# DDR_MIO.net
KiCad netlist of a schematic drawn in Altium Designer
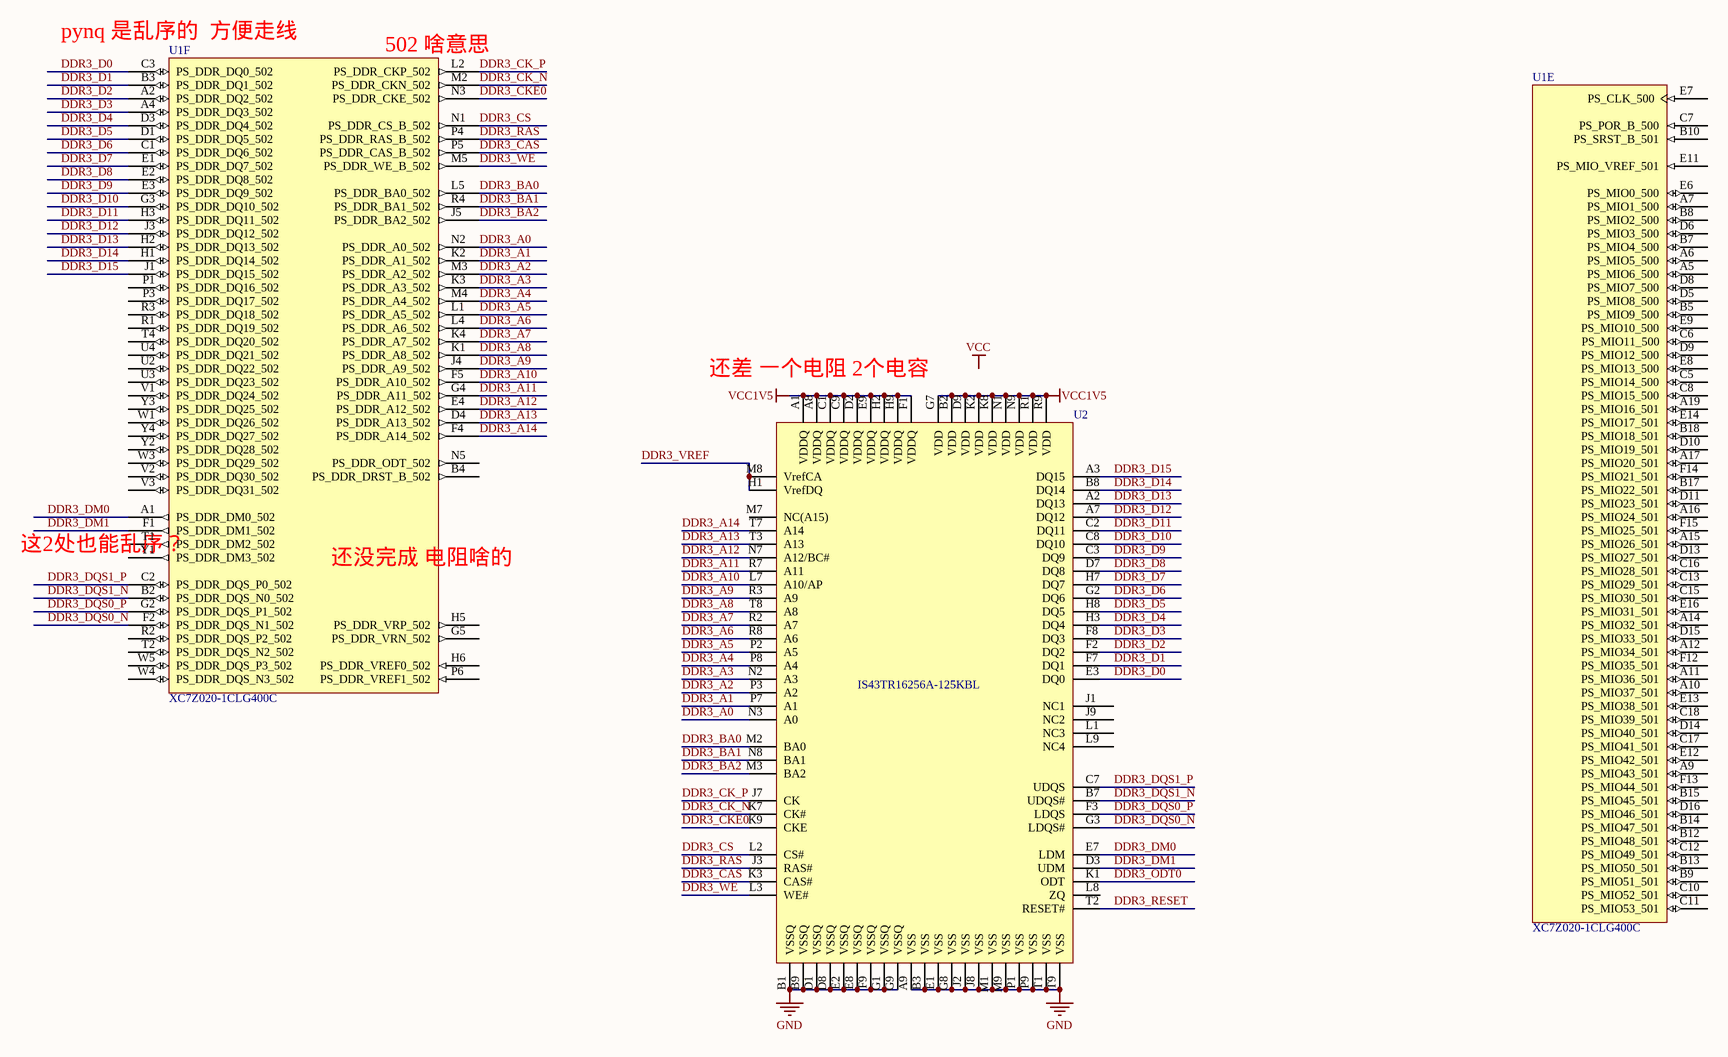
[diagram p0: DDR&MIO.SchDoc]

(export (version "E")
  (design (tool "Eeschema 10.0.6"))
  (components
    (comp (ref "U1")
      (value "XC7Z020-1CLG400C")
      (footprint "CLG400")
      (fields (field (name "GENERIC PART NUMBER") "XC7Z020") (field (name "MANUFACTURER") "Xilinx"))
      (libsource (lib "Zynq-7000") (part "XC7Z020-1CLG400C"))
    )
    (comp (ref "U2")
      (value "IS43TR16256A-125KBL")
      (footprint "BGA96C80P16X9_1400X900X120")
      (description "与MT41K256M16HA-125IT完全兼容")
      (libsource (lib "misc1") (part "IS43TR16256A-125KBL"))
    )
  )
  (nets
    (net (code "1") (name "/DDR3_A0") (class "Default")
      (node (ref "U1") (pin "N2") (pinfunction "PS_DDR_A0_502_N2") (pintype "output"))
      (node (ref "U2") (pin "N3") (pinfunction "A0_N3") (pintype "passive"))
    )
    (net (code "2") (name "/DDR3_A1") (class "Default")
      (node (ref "U1") (pin "K2") (pinfunction "PS_DDR_A1_502_K2") (pintype "output"))
      (node (ref "U2") (pin "P7") (pinfunction "A1_P7") (pintype "passive"))
    )
    (net (code "3") (name "/DDR3_A2") (class "Default")
      (node (ref "U1") (pin "M3") (pinfunction "PS_DDR_A2_502_M3") (pintype "output"))
      (node (ref "U2") (pin "P3") (pinfunction "A2_P3") (pintype "passive"))
    )
    (net (code "4") (name "/DDR3_A3") (class "Default")
      (node (ref "U1") (pin "K3") (pinfunction "PS_DDR_A3_502_K3") (pintype "output"))
      (node (ref "U2") (pin "N2") (pinfunction "A3_N2") (pintype "passive"))
    )
    (net (code "5") (name "/DDR3_A4") (class "Default")
      (node (ref "U1") (pin "M4") (pinfunction "PS_DDR_A4_502_M4") (pintype "output"))
      (node (ref "U2") (pin "P8") (pinfunction "A4_P8") (pintype "passive"))
    )
    (net (code "6") (name "/DDR3_A5") (class "Default")
      (node (ref "U1") (pin "L1") (pinfunction "PS_DDR_A5_502_L1") (pintype "output"))
      (node (ref "U2") (pin "P2") (pinfunction "A5_P2") (pintype "passive"))
    )
    (net (code "7") (name "/DDR3_A6") (class "Default")
      (node (ref "U1") (pin "L4") (pinfunction "PS_DDR_A6_502_L4") (pintype "output"))
      (node (ref "U2") (pin "R8") (pinfunction "A6_R8") (pintype "passive"))
    )
    (net (code "8") (name "/DDR3_A7") (class "Default")
      (node (ref "U1") (pin "K4") (pinfunction "PS_DDR_A7_502_K4") (pintype "output"))
      (node (ref "U2") (pin "R2") (pinfunction "A7_R2") (pintype "passive"))
    )
    (net (code "9") (name "/DDR3_A8") (class "Default")
      (node (ref "U1") (pin "K1") (pinfunction "PS_DDR_A8_502_K1") (pintype "output"))
      (node (ref "U2") (pin "T8") (pinfunction "A8_T8") (pintype "passive"))
    )
    (net (code "10") (name "/DDR3_A9") (class "Default")
      (node (ref "U1") (pin "J4") (pinfunction "PS_DDR_A9_502_J4") (pintype "output"))
      (node (ref "U2") (pin "R3") (pinfunction "A9_R3") (pintype "passive"))
    )
    (net (code "11") (name "/DDR3_A10") (class "Default")
      (node (ref "U1") (pin "F5") (pinfunction "PS_DDR_A10_502_F5") (pintype "output"))
      (node (ref "U2") (pin "L7") (pinfunction "A10/AP_L7") (pintype "passive"))
    )
    (net (code "12") (name "/DDR3_A11") (class "Default")
      (node (ref "U1") (pin "G4") (pinfunction "PS_DDR_A11_502_G4") (pintype "output"))
      (node (ref "U2") (pin "R7") (pinfunction "A11_R7") (pintype "passive"))
    )
    (net (code "13") (name "/DDR3_A12") (class "Default")
      (node (ref "U1") (pin "E4") (pinfunction "PS_DDR_A12_502_E4") (pintype "output"))
      (node (ref "U2") (pin "N7") (pinfunction "A12/BC#_N7") (pintype "passive"))
    )
    (net (code "14") (name "/DDR3_A13") (class "Default")
      (node (ref "U1") (pin "D4") (pinfunction "PS_DDR_A13_502_D4") (pintype "output"))
      (node (ref "U2") (pin "T3") (pinfunction "A13_T3") (pintype "passive"))
    )
    (net (code "15") (name "/DDR3_A14") (class "Default")
      (node (ref "U1") (pin "F4") (pinfunction "PS_DDR_A14_502_F4") (pintype "output"))
      (node (ref "U2") (pin "T7") (pinfunction "A14_T7") (pintype "passive"))
    )
    (net (code "16") (name "/DDR3_BA0") (class "Default")
      (node (ref "U1") (pin "L5") (pinfunction "PS_DDR_BA0_502_L5") (pintype "output"))
      (node (ref "U2") (pin "M2") (pinfunction "BA0_M2") (pintype "passive"))
    )
    (net (code "17") (name "/DDR3_BA1") (class "Default")
      (node (ref "U1") (pin "R4") (pinfunction "PS_DDR_BA1_502_R4") (pintype "output"))
      (node (ref "U2") (pin "N8") (pinfunction "BA1_N8") (pintype "passive"))
    )
    (net (code "18") (name "/DDR3_BA2") (class "Default")
      (node (ref "U1") (pin "J5") (pinfunction "PS_DDR_BA2_502_J5") (pintype "output"))
      (node (ref "U2") (pin "M3") (pinfunction "BA2_M3") (pintype "passive"))
    )
    (net (code "19") (name "/DDR3_CAS") (class "Default")
      (node (ref "U1") (pin "P5") (pinfunction "PS_DDR_CAS_B_502_P5") (pintype "output"))
      (node (ref "U2") (pin "K3") (pinfunction "CAS#_K3") (pintype "passive"))
    )
    (net (code "20") (name "/DDR3_CKE0") (class "Default")
      (node (ref "U1") (pin "N3") (pinfunction "PS_DDR_CKE_502_N3") (pintype "output"))
      (node (ref "U2") (pin "K9") (pinfunction "CKE_K9") (pintype "passive"))
    )
    (net (code "21") (name "/DDR3_CK_N") (class "Default")
      (node (ref "U1") (pin "M2") (pinfunction "PS_DDR_CKN_502_M2") (pintype "output"))
      (node (ref "U2") (pin "K7") (pinfunction "CK#_K7") (pintype "passive"))
    )
    (net (code "22") (name "/DDR3_CK_P") (class "Default")
      (node (ref "U1") (pin "L2") (pinfunction "PS_DDR_CKP_502_L2") (pintype "output"))
      (node (ref "U2") (pin "J7") (pinfunction "CK_J7") (pintype "passive"))
    )
    (net (code "23") (name "/DDR3_CS") (class "Default")
      (node (ref "U1") (pin "N1") (pinfunction "PS_DDR_CS_B_502_N1") (pintype "output"))
      (node (ref "U2") (pin "L2") (pinfunction "CS#_L2") (pintype "passive"))
    )
    (net (code "24") (name "/DDR3_D0") (class "Default")
      (node (ref "U1") (pin "C3") (pinfunction "PS_DDR_DQ0_502_C3") (pintype "bidirectional"))
      (node (ref "U2") (pin "E3") (pinfunction "DQ0_E3") (pintype "passive"))
    )
    (net (code "25") (name "/DDR3_D1") (class "Default")
      (node (ref "U1") (pin "B3") (pinfunction "PS_DDR_DQ1_502_B3") (pintype "bidirectional"))
      (node (ref "U2") (pin "F7") (pinfunction "DQ1_F7") (pintype "passive"))
    )
    (net (code "26") (name "/DDR3_D2") (class "Default")
      (node (ref "U1") (pin "A2") (pinfunction "PS_DDR_DQ2_502_A2") (pintype "bidirectional"))
      (node (ref "U2") (pin "F2") (pinfunction "DQ2_F2") (pintype "passive"))
    )
    (net (code "27") (name "/DDR3_D3") (class "Default")
      (node (ref "U1") (pin "A4") (pinfunction "PS_DDR_DQ3_502_A4") (pintype "bidirectional"))
      (node (ref "U2") (pin "F8") (pinfunction "DQ3_F8") (pintype "passive"))
    )
    (net (code "28") (name "/DDR3_D4") (class "Default")
      (node (ref "U1") (pin "D3") (pinfunction "PS_DDR_DQ4_502_D3") (pintype "bidirectional"))
      (node (ref "U2") (pin "H3") (pinfunction "DQ4_H3") (pintype "passive"))
    )
    (net (code "29") (name "/DDR3_D5") (class "Default")
      (node (ref "U1") (pin "D1") (pinfunction "PS_DDR_DQ5_502_D1") (pintype "bidirectional"))
      (node (ref "U2") (pin "H8") (pinfunction "DQ5_H8") (pintype "passive"))
    )
    (net (code "30") (name "/DDR3_D6") (class "Default")
      (node (ref "U1") (pin "C1") (pinfunction "PS_DDR_DQ6_502_C1") (pintype "bidirectional"))
      (node (ref "U2") (pin "G2") (pinfunction "DQ6_G2") (pintype "passive"))
    )
    (net (code "31") (name "/DDR3_D7") (class "Default")
      (node (ref "U1") (pin "E1") (pinfunction "PS_DDR_DQ7_502_E1") (pintype "bidirectional"))
      (node (ref "U2") (pin "H7") (pinfunction "DQ7_H7") (pintype "passive"))
    )
    (net (code "32") (name "/DDR3_D8") (class "Default")
      (node (ref "U1") (pin "E2") (pinfunction "PS_DDR_DQ8_502_E2") (pintype "bidirectional"))
      (node (ref "U2") (pin "D7") (pinfunction "DQ8_D7") (pintype "passive"))
    )
    (net (code "33") (name "/DDR3_D9") (class "Default")
      (node (ref "U1") (pin "E3") (pinfunction "PS_DDR_DQ9_502_E3") (pintype "bidirectional"))
      (node (ref "U2") (pin "C3") (pinfunction "DQ9_C3") (pintype "passive"))
    )
    (net (code "34") (name "/DDR3_D10") (class "Default")
      (node (ref "U1") (pin "G3") (pinfunction "PS_DDR_DQ10_502_G3") (pintype "bidirectional"))
      (node (ref "U2") (pin "C8") (pinfunction "DQ10_C8") (pintype "passive"))
    )
    (net (code "35") (name "/DDR3_D11") (class "Default")
      (node (ref "U1") (pin "H3") (pinfunction "PS_DDR_DQ11_502_H3") (pintype "bidirectional"))
      (node (ref "U2") (pin "C2") (pinfunction "DQ11_C2") (pintype "passive"))
    )
    (net (code "36") (name "/DDR3_D12") (class "Default")
      (node (ref "U1") (pin "J3") (pinfunction "PS_DDR_DQ12_502_J3") (pintype "bidirectional"))
      (node (ref "U2") (pin "A7") (pinfunction "DQ12_A7") (pintype "passive"))
    )
    (net (code "37") (name "/DDR3_D13") (class "Default")
      (node (ref "U1") (pin "H2") (pinfunction "PS_DDR_DQ13_502_H2") (pintype "bidirectional"))
      (node (ref "U2") (pin "A2") (pinfunction "DQ13_A2") (pintype "passive"))
    )
    (net (code "38") (name "/DDR3_D14") (class "Default")
      (node (ref "U1") (pin "H1") (pinfunction "PS_DDR_DQ14_502_H1") (pintype "bidirectional"))
      (node (ref "U2") (pin "B8") (pinfunction "DQ14_B8") (pintype "passive"))
    )
    (net (code "39") (name "/DDR3_D15") (class "Default")
      (node (ref "U1") (pin "J1") (pinfunction "PS_DDR_DQ15_502_J1") (pintype "bidirectional"))
      (node (ref "U2") (pin "A3") (pinfunction "DQ15_A3") (pintype "passive"))
    )
    (net (code "40") (name "/DDR3_DM0") (class "Default")
      (node (ref "U1") (pin "A1") (pinfunction "PS_DDR_DM0_502_A1") (pintype "output"))
      (node (ref "U2") (pin "E7") (pinfunction "LDM_E7") (pintype "passive"))
    )
    (net (code "41") (name "/DDR3_DM1") (class "Default")
      (node (ref "U1") (pin "F1") (pinfunction "PS_DDR_DM1_502_F1") (pintype "output"))
      (node (ref "U2") (pin "D3") (pinfunction "UDM_D3") (pintype "passive"))
    )
    (net (code "42") (name "/DDR3_DQS0_N") (class "Default")
      (node (ref "U1") (pin "F2") (pinfunction "PS_DDR_DQS_N1_502_F2") (pintype "bidirectional"))
      (node (ref "U2") (pin "G3") (pinfunction "LDQS#_G3") (pintype "passive"))
    )
    (net (code "43") (name "/DDR3_DQS0_P") (class "Default")
      (node (ref "U1") (pin "G2") (pinfunction "PS_DDR_DQS_P1_502_G2") (pintype "bidirectional"))
      (node (ref "U2") (pin "F3") (pinfunction "LDQS_F3") (pintype "passive"))
    )
    (net (code "44") (name "/DDR3_DQS1_N") (class "Default")
      (node (ref "U1") (pin "B2") (pinfunction "PS_DDR_DQS_N0_502_B2") (pintype "bidirectional"))
      (node (ref "U2") (pin "B7") (pinfunction "UDQS#_B7") (pintype "passive"))
    )
    (net (code "45") (name "/DDR3_DQS1_P") (class "Default")
      (node (ref "U1") (pin "C2") (pinfunction "PS_DDR_DQS_P0_502_C2") (pintype "bidirectional"))
      (node (ref "U2") (pin "C7") (pinfunction "UDQS_C7") (pintype "passive"))
    )
    (net (code "46") (name "/DDR3_ODT0") (class "Default")
      (node (ref "U2") (pin "K1") (pinfunction "ODT_K1") (pintype "passive"))
    )
    (net (code "47") (name "/DDR3_RAS") (class "Default")
      (node (ref "U1") (pin "P4") (pinfunction "PS_DDR_RAS_B_502_P4") (pintype "output"))
      (node (ref "U2") (pin "J3") (pinfunction "RAS#_J3") (pintype "passive"))
    )
    (net (code "48") (name "/DDR3_RESET") (class "Default")
      (node (ref "U2") (pin "T2") (pinfunction "RESET#_T2") (pintype "passive"))
    )
    (net (code "49") (name "/DDR3_VREF") (class "Default")
      (node (ref "U2") (pin "H1") (pinfunction "VrefDQ_H1") (pintype "passive"))
      (node (ref "U2") (pin "M8") (pinfunction "VrefCA_M8") (pintype "passive"))
    )
    (net (code "50") (name "/DDR3_WE") (class "Default")
      (node (ref "U1") (pin "M5") (pinfunction "PS_DDR_WE_B_502_M5") (pintype "output"))
      (node (ref "U2") (pin "L3") (pinfunction "WE#_L3") (pintype "passive"))
    )
    (net (code "51") (name "GND") (class "Default")
      (node (ref "U2") (pin "A9") (pinfunction "VSS_A9") (pintype "passive"))
      (node (ref "U2") (pin "B1") (pinfunction "VSSQ_B1") (pintype "passive"))
      (node (ref "U2") (pin "B3") (pinfunction "VSS_B3") (pintype "passive"))
      (node (ref "U2") (pin "B9") (pinfunction "VSSQ_B9") (pintype "passive"))
      (node (ref "U2") (pin "D1") (pinfunction "VSSQ_D1") (pintype "passive"))
      (node (ref "U2") (pin "D8") (pinfunction "VSSQ_D8") (pintype "passive"))
      (node (ref "U2") (pin "E1") (pinfunction "VSS_E1") (pintype "passive"))
      (node (ref "U2") (pin "E2") (pinfunction "VSSQ_E2") (pintype "passive"))
      (node (ref "U2") (pin "E8") (pinfunction "VSSQ_E8") (pintype "passive"))
      (node (ref "U2") (pin "F9") (pinfunction "VSSQ_F9") (pintype "passive"))
      (node (ref "U2") (pin "G1") (pinfunction "VSSQ_G1") (pintype "passive"))
      (node (ref "U2") (pin "G8") (pinfunction "VSS_G8") (pintype "passive"))
      (node (ref "U2") (pin "G9") (pinfunction "VSSQ_G9") (pintype "passive"))
      (node (ref "U2") (pin "J2") (pinfunction "VSS_J2") (pintype "passive"))
      (node (ref "U2") (pin "J8") (pinfunction "VSS_J8") (pintype "passive"))
      (node (ref "U2") (pin "M1") (pinfunction "VSS_M1") (pintype "passive"))
      (node (ref "U2") (pin "M9") (pinfunction "VSS_M9") (pintype "passive"))
      (node (ref "U2") (pin "P1") (pinfunction "VSS_P1") (pintype "passive"))
      (node (ref "U2") (pin "P9") (pinfunction "VSS_P9") (pintype "passive"))
      (node (ref "U2") (pin "T1") (pinfunction "VSS_T1") (pintype "passive"))
      (node (ref "U2") (pin "T9") (pinfunction "VSS_T9") (pintype "passive"))
    )
    (net (code "53") (name "VCC1V5") (class "Default")
      (node (ref "U2") (pin "A1") (pinfunction "VDDQ_A1") (pintype "passive"))
      (node (ref "U2") (pin "A8") (pinfunction "VDDQ_A8") (pintype "passive"))
      (node (ref "U2") (pin "B2") (pinfunction "VDD_B2") (pintype "passive"))
      (node (ref "U2") (pin "C1") (pinfunction "VDDQ_C1") (pintype "passive"))
      (node (ref "U2") (pin "C9") (pinfunction "VDDQ_C9") (pintype "passive"))
      (node (ref "U2") (pin "D2") (pinfunction "VDDQ_D2") (pintype "passive"))
      (node (ref "U2") (pin "D9") (pinfunction "VDD_D9") (pintype "passive"))
      (node (ref "U2") (pin "E9") (pinfunction "VDDQ_E9") (pintype "passive"))
      (node (ref "U2") (pin "F1") (pinfunction "VDDQ_F1") (pintype "passive"))
      (node (ref "U2") (pin "G7") (pinfunction "VDD_G7") (pintype "passive"))
      (node (ref "U2") (pin "H2") (pinfunction "VDDQ_H2") (pintype "passive"))
      (node (ref "U2") (pin "H9") (pinfunction "VDDQ_H9") (pintype "passive"))
      (node (ref "U2") (pin "K2") (pinfunction "VDD_K2") (pintype "passive"))
      (node (ref "U2") (pin "K8") (pinfunction "VDD_K8") (pintype "passive"))
      (node (ref "U2") (pin "N1") (pinfunction "VDD_N1") (pintype "passive"))
      (node (ref "U2") (pin "N9") (pinfunction "VDD_N9") (pintype "passive"))
      (node (ref "U2") (pin "R1") (pinfunction "VDD_R1") (pintype "passive"))
      (node (ref "U2") (pin "R9") (pinfunction "VDD_R9") (pintype "passive"))
    )
    (net (code "54") (name "unconnected-(U1E-PS_CLK_500-PadE7)") (class "Default")
      (node (ref "U1") (pin "E7") (pinfunction "PS_CLK_500_E7") (pintype "input"))
    )
    (net (code "55") (name "unconnected-(U1E-PS_MIO0_500-PadE6)") (class "Default")
      (node (ref "U1") (pin "E6") (pinfunction "PS_MIO0_500_E6") (pintype "bidirectional"))
    )
    (net (code "56") (name "unconnected-(U1E-PS_MIO1_500-PadA7)") (class "Default")
      (node (ref "U1") (pin "A7") (pinfunction "PS_MIO1_500_A7") (pintype "bidirectional"))
    )
    (net (code "57") (name "unconnected-(U1E-PS_MIO2_500-PadB8)") (class "Default")
      (node (ref "U1") (pin "B8") (pinfunction "PS_MIO2_500_B8") (pintype "bidirectional"))
    )
    (net (code "58") (name "unconnected-(U1E-PS_MIO3_500-PadD6)") (class "Default")
      (node (ref "U1") (pin "D6") (pinfunction "PS_MIO3_500_D6") (pintype "bidirectional"))
    )
    (net (code "59") (name "unconnected-(U1E-PS_MIO4_500-PadB7)") (class "Default")
      (node (ref "U1") (pin "B7") (pinfunction "PS_MIO4_500_B7") (pintype "bidirectional"))
    )
    (net (code "60") (name "unconnected-(U1E-PS_MIO5_500-PadA6)") (class "Default")
      (node (ref "U1") (pin "A6") (pinfunction "PS_MIO5_500_A6") (pintype "bidirectional"))
    )
    (net (code "61") (name "unconnected-(U1E-PS_MIO6_500-PadA5)") (class "Default")
      (node (ref "U1") (pin "A5") (pinfunction "PS_MIO6_500_A5") (pintype "bidirectional"))
    )
    (net (code "62") (name "unconnected-(U1E-PS_MIO7_500-PadD8)") (class "Default")
      (node (ref "U1") (pin "D8") (pinfunction "PS_MIO7_500_D8") (pintype "bidirectional"))
    )
    (net (code "63") (name "unconnected-(U1E-PS_MIO8_500-PadD5)") (class "Default")
      (node (ref "U1") (pin "D5") (pinfunction "PS_MIO8_500_D5") (pintype "bidirectional"))
    )
    (net (code "64") (name "unconnected-(U1E-PS_MIO9_500-PadB5)") (class "Default")
      (node (ref "U1") (pin "B5") (pinfunction "PS_MIO9_500_B5") (pintype "bidirectional"))
    )
    (net (code "65") (name "unconnected-(U1E-PS_MIO10_500-PadE9)") (class "Default")
      (node (ref "U1") (pin "E9") (pinfunction "PS_MIO10_500_E9") (pintype "bidirectional"))
    )
    (net (code "66") (name "unconnected-(U1E-PS_MIO11_500-PadC6)") (class "Default")
      (node (ref "U1") (pin "C6") (pinfunction "PS_MIO11_500_C6") (pintype "bidirectional"))
    )
    (net (code "67") (name "unconnected-(U1E-PS_MIO12_500-PadD9)") (class "Default")
      (node (ref "U1") (pin "D9") (pinfunction "PS_MIO12_500_D9") (pintype "bidirectional"))
    )
    (net (code "68") (name "unconnected-(U1E-PS_MIO13_500-PadE8)") (class "Default")
      (node (ref "U1") (pin "E8") (pinfunction "PS_MIO13_500_E8") (pintype "bidirectional"))
    )
    (net (code "69") (name "unconnected-(U1E-PS_MIO14_500-PadC5)") (class "Default")
      (node (ref "U1") (pin "C5") (pinfunction "PS_MIO14_500_C5") (pintype "bidirectional"))
    )
    (net (code "70") (name "unconnected-(U1E-PS_MIO15_500-PadC8)") (class "Default")
      (node (ref "U1") (pin "C8") (pinfunction "PS_MIO15_500_C8") (pintype "bidirectional"))
    )
    (net (code "71") (name "unconnected-(U1E-PS_MIO16_501-PadA19)") (class "Default")
      (node (ref "U1") (pin "A19") (pinfunction "PS_MIO16_501_A19") (pintype "bidirectional"))
    )
    (net (code "72") (name "unconnected-(U1E-PS_MIO17_501-PadE14)") (class "Default")
      (node (ref "U1") (pin "E14") (pinfunction "PS_MIO17_501_E14") (pintype "bidirectional"))
    )
    (net (code "73") (name "unconnected-(U1E-PS_MIO18_501-PadB18)") (class "Default")
      (node (ref "U1") (pin "B18") (pinfunction "PS_MIO18_501_B18") (pintype "bidirectional"))
    )
    (net (code "74") (name "unconnected-(U1E-PS_MIO19_501-PadD10)") (class "Default")
      (node (ref "U1") (pin "D10") (pinfunction "PS_MIO19_501_D10") (pintype "bidirectional"))
    )
    (net (code "75") (name "unconnected-(U1E-PS_MIO20_501-PadA17)") (class "Default")
      (node (ref "U1") (pin "A17") (pinfunction "PS_MIO20_501_A17") (pintype "bidirectional"))
    )
    (net (code "76") (name "unconnected-(U1E-PS_MIO21_501-PadF14)") (class "Default")
      (node (ref "U1") (pin "F14") (pinfunction "PS_MIO21_501_F14") (pintype "bidirectional"))
    )
    (net (code "77") (name "unconnected-(U1E-PS_MIO22_501-PadB17)") (class "Default")
      (node (ref "U1") (pin "B17") (pinfunction "PS_MIO22_501_B17") (pintype "bidirectional"))
    )
    (net (code "78") (name "unconnected-(U1E-PS_MIO23_501-PadD11)") (class "Default")
      (node (ref "U1") (pin "D11") (pinfunction "PS_MIO23_501_D11") (pintype "bidirectional"))
    )
    (net (code "79") (name "unconnected-(U1E-PS_MIO24_501-PadA16)") (class "Default")
      (node (ref "U1") (pin "A16") (pinfunction "PS_MIO24_501_A16") (pintype "bidirectional"))
    )
    (net (code "80") (name "unconnected-(U1E-PS_MIO25_501-PadF15)") (class "Default")
      (node (ref "U1") (pin "F15") (pinfunction "PS_MIO25_501_F15") (pintype "bidirectional"))
    )
    (net (code "81") (name "unconnected-(U1E-PS_MIO26_501-PadA15)") (class "Default")
      (node (ref "U1") (pin "A15") (pinfunction "PS_MIO26_501_A15") (pintype "bidirectional"))
    )
    (net (code "82") (name "unconnected-(U1E-PS_MIO27_501-PadD13)") (class "Default")
      (node (ref "U1") (pin "D13") (pinfunction "PS_MIO27_501_D13") (pintype "bidirectional"))
    )
    (net (code "83") (name "unconnected-(U1E-PS_MIO28_501-PadC16)") (class "Default")
      (node (ref "U1") (pin "C16") (pinfunction "PS_MIO28_501_C16") (pintype "bidirectional"))
    )
    (net (code "84") (name "unconnected-(U1E-PS_MIO29_501-PadC13)") (class "Default")
      (node (ref "U1") (pin "C13") (pinfunction "PS_MIO29_501_C13") (pintype "bidirectional"))
    )
    (net (code "85") (name "unconnected-(U1E-PS_MIO30_501-PadC15)") (class "Default")
      (node (ref "U1") (pin "C15") (pinfunction "PS_MIO30_501_C15") (pintype "bidirectional"))
    )
    (net (code "86") (name "unconnected-(U1E-PS_MIO31_501-PadE16)") (class "Default")
      (node (ref "U1") (pin "E16") (pinfunction "PS_MIO31_501_E16") (pintype "bidirectional"))
    )
    (net (code "87") (name "unconnected-(U1E-PS_MIO32_501-PadA14)") (class "Default")
      (node (ref "U1") (pin "A14") (pinfunction "PS_MIO32_501_A14") (pintype "bidirectional"))
    )
    (net (code "88") (name "unconnected-(U1E-PS_MIO33_501-PadD15)") (class "Default")
      (node (ref "U1") (pin "D15") (pinfunction "PS_MIO33_501_D15") (pintype "bidirectional"))
    )
    (net (code "89") (name "unconnected-(U1E-PS_MIO34_501-PadA12)") (class "Default")
      (node (ref "U1") (pin "A12") (pinfunction "PS_MIO34_501_A12") (pintype "bidirectional"))
    )
    (net (code "90") (name "unconnected-(U1E-PS_MIO35_501-PadF12)") (class "Default")
      (node (ref "U1") (pin "F12") (pinfunction "PS_MIO35_501_F12") (pintype "bidirectional"))
    )
    (net (code "91") (name "unconnected-(U1E-PS_MIO36_501-PadA11)") (class "Default")
      (node (ref "U1") (pin "A11") (pinfunction "PS_MIO36_501_A11") (pintype "bidirectional"))
    )
    (net (code "92") (name "unconnected-(U1E-PS_MIO37_501-PadA10)") (class "Default")
      (node (ref "U1") (pin "A10") (pinfunction "PS_MIO37_501_A10") (pintype "bidirectional"))
    )
    (net (code "93") (name "unconnected-(U1E-PS_MIO38_501-PadE13)") (class "Default")
      (node (ref "U1") (pin "E13") (pinfunction "PS_MIO38_501_E13") (pintype "bidirectional"))
    )
    (net (code "94") (name "unconnected-(U1E-PS_MIO39_501-PadC18)") (class "Default")
      (node (ref "U1") (pin "C18") (pinfunction "PS_MIO39_501_C18") (pintype "bidirectional"))
    )
    (net (code "95") (name "unconnected-(U1E-PS_MIO40_501-PadD14)") (class "Default")
      (node (ref "U1") (pin "D14") (pinfunction "PS_MIO40_501_D14") (pintype "bidirectional"))
    )
    (net (code "96") (name "unconnected-(U1E-PS_MIO41_501-PadC17)") (class "Default")
      (node (ref "U1") (pin "C17") (pinfunction "PS_MIO41_501_C17") (pintype "bidirectional"))
    )
    (net (code "97") (name "unconnected-(U1E-PS_MIO42_501-PadE12)") (class "Default")
      (node (ref "U1") (pin "E12") (pinfunction "PS_MIO42_501_E12") (pintype "bidirectional"))
    )
    (net (code "98") (name "unconnected-(U1E-PS_MIO43_501-PadA9)") (class "Default")
      (node (ref "U1") (pin "A9") (pinfunction "PS_MIO43_501_A9") (pintype "bidirectional"))
    )
    (net (code "99") (name "unconnected-(U1E-PS_MIO44_501-PadF13)") (class "Default")
      (node (ref "U1") (pin "F13") (pinfunction "PS_MIO44_501_F13") (pintype "bidirectional"))
    )
    (net (code "100") (name "unconnected-(U1E-PS_MIO45_501-PadB15)") (class "Default")
      (node (ref "U1") (pin "B15") (pinfunction "PS_MIO45_501_B15") (pintype "bidirectional"))
    )
    (net (code "101") (name "unconnected-(U1E-PS_MIO46_501-PadD16)") (class "Default")
      (node (ref "U1") (pin "D16") (pinfunction "PS_MIO46_501_D16") (pintype "bidirectional"))
    )
    (net (code "102") (name "unconnected-(U1E-PS_MIO47_501-PadB14)") (class "Default")
      (node (ref "U1") (pin "B14") (pinfunction "PS_MIO47_501_B14") (pintype "bidirectional"))
    )
    (net (code "103") (name "unconnected-(U1E-PS_MIO48_501-PadB12)") (class "Default")
      (node (ref "U1") (pin "B12") (pinfunction "PS_MIO48_501_B12") (pintype "bidirectional"))
    )
    (net (code "104") (name "unconnected-(U1E-PS_MIO49_501-PadC12)") (class "Default")
      (node (ref "U1") (pin "C12") (pinfunction "PS_MIO49_501_C12") (pintype "bidirectional"))
    )
    (net (code "105") (name "unconnected-(U1E-PS_MIO50_501-PadB13)") (class "Default")
      (node (ref "U1") (pin "B13") (pinfunction "PS_MIO50_501_B13") (pintype "bidirectional"))
    )
    (net (code "106") (name "unconnected-(U1E-PS_MIO51_501-PadB9)") (class "Default")
      (node (ref "U1") (pin "B9") (pinfunction "PS_MIO51_501_B9") (pintype "bidirectional"))
    )
    (net (code "107") (name "unconnected-(U1E-PS_MIO52_501-PadC10)") (class "Default")
      (node (ref "U1") (pin "C10") (pinfunction "PS_MIO52_501_C10") (pintype "bidirectional"))
    )
    (net (code "108") (name "unconnected-(U1E-PS_MIO53_501-PadC11)") (class "Default")
      (node (ref "U1") (pin "C11") (pinfunction "PS_MIO53_501_C11") (pintype "bidirectional"))
    )
    (net (code "109") (name "unconnected-(U1E-PS_MIO_VREF_501-PadE11)") (class "Default")
      (node (ref "U1") (pin "E11") (pinfunction "PS_MIO_VREF_501_E11") (pintype "input"))
    )
    (net (code "110") (name "unconnected-(U1E-PS_POR_B_500-PadC7)") (class "Default")
      (node (ref "U1") (pin "C7") (pinfunction "PS_POR_B_500_C7") (pintype "input"))
    )
    (net (code "111") (name "unconnected-(U1E-PS_SRST_B_501-PadB10)") (class "Default")
      (node (ref "U1") (pin "B10") (pinfunction "PS_SRST_B_501_B10") (pintype "input"))
    )
    (net (code "112") (name "unconnected-(U1F-PS_DDR_DM2_502-PadT1)") (class "Default")
      (node (ref "U1") (pin "T1") (pinfunction "PS_DDR_DM2_502_T1") (pintype "output"))
    )
    (net (code "113") (name "unconnected-(U1F-PS_DDR_DM3_502-PadY1)") (class "Default")
      (node (ref "U1") (pin "Y1") (pinfunction "PS_DDR_DM3_502_Y1") (pintype "output"))
    )
    (net (code "114") (name "unconnected-(U1F-PS_DDR_DQ16_502-PadP1)") (class "Default")
      (node (ref "U1") (pin "P1") (pinfunction "PS_DDR_DQ16_502_P1") (pintype "bidirectional"))
    )
    (net (code "115") (name "unconnected-(U1F-PS_DDR_DQ17_502-PadP3)") (class "Default")
      (node (ref "U1") (pin "P3") (pinfunction "PS_DDR_DQ17_502_P3") (pintype "bidirectional"))
    )
    (net (code "116") (name "unconnected-(U1F-PS_DDR_DQ18_502-PadR3)") (class "Default")
      (node (ref "U1") (pin "R3") (pinfunction "PS_DDR_DQ18_502_R3") (pintype "bidirectional"))
    )
    (net (code "117") (name "unconnected-(U1F-PS_DDR_DQ19_502-PadR1)") (class "Default")
      (node (ref "U1") (pin "R1") (pinfunction "PS_DDR_DQ19_502_R1") (pintype "bidirectional"))
    )
    (net (code "118") (name "unconnected-(U1F-PS_DDR_DQ20_502-PadT4)") (class "Default")
      (node (ref "U1") (pin "T4") (pinfunction "PS_DDR_DQ20_502_T4") (pintype "bidirectional"))
    )
    (net (code "119") (name "unconnected-(U1F-PS_DDR_DQ21_502-PadU4)") (class "Default")
      (node (ref "U1") (pin "U4") (pinfunction "PS_DDR_DQ21_502_U4") (pintype "bidirectional"))
    )
    (net (code "120") (name "unconnected-(U1F-PS_DDR_DQ22_502-PadU2)") (class "Default")
      (node (ref "U1") (pin "U2") (pinfunction "PS_DDR_DQ22_502_U2") (pintype "bidirectional"))
    )
    (net (code "121") (name "unconnected-(U1F-PS_DDR_DQ23_502-PadU3)") (class "Default")
      (node (ref "U1") (pin "U3") (pinfunction "PS_DDR_DQ23_502_U3") (pintype "bidirectional"))
    )
    (net (code "122") (name "unconnected-(U1F-PS_DDR_DQ24_502-PadV1)") (class "Default")
      (node (ref "U1") (pin "V1") (pinfunction "PS_DDR_DQ24_502_V1") (pintype "bidirectional"))
    )
    (net (code "123") (name "unconnected-(U1F-PS_DDR_DQ25_502-PadY3)") (class "Default")
      (node (ref "U1") (pin "Y3") (pinfunction "PS_DDR_DQ25_502_Y3") (pintype "bidirectional"))
    )
    (net (code "124") (name "unconnected-(U1F-PS_DDR_DQ26_502-PadW1)") (class "Default")
      (node (ref "U1") (pin "W1") (pinfunction "PS_DDR_DQ26_502_W1") (pintype "bidirectional"))
    )
    (net (code "125") (name "unconnected-(U1F-PS_DDR_DQ27_502-PadY4)") (class "Default")
      (node (ref "U1") (pin "Y4") (pinfunction "PS_DDR_DQ27_502_Y4") (pintype "bidirectional"))
    )
    (net (code "126") (name "unconnected-(U1F-PS_DDR_DQ28_502-PadY2)") (class "Default")
      (node (ref "U1") (pin "Y2") (pinfunction "PS_DDR_DQ28_502_Y2") (pintype "bidirectional"))
    )
    (net (code "127") (name "unconnected-(U1F-PS_DDR_DQ29_502-PadW3)") (class "Default")
      (node (ref "U1") (pin "W3") (pinfunction "PS_DDR_DQ29_502_W3") (pintype "bidirectional"))
    )
    (net (code "128") (name "unconnected-(U1F-PS_DDR_DQ30_502-PadV2)") (class "Default")
      (node (ref "U1") (pin "V2") (pinfunction "PS_DDR_DQ30_502_V2") (pintype "bidirectional"))
    )
    (net (code "129") (name "unconnected-(U1F-PS_DDR_DQ31_502-PadV3)") (class "Default")
      (node (ref "U1") (pin "V3") (pinfunction "PS_DDR_DQ31_502_V3") (pintype "bidirectional"))
    )
    (net (code "130") (name "unconnected-(U1F-PS_DDR_DQS_N2_502-PadT2)") (class "Default")
      (node (ref "U1") (pin "T2") (pinfunction "PS_DDR_DQS_N2_502_T2") (pintype "bidirectional"))
    )
    (net (code "131") (name "unconnected-(U1F-PS_DDR_DQS_N3_502-PadW4)") (class "Default")
      (node (ref "U1") (pin "W4") (pinfunction "PS_DDR_DQS_N3_502_W4") (pintype "bidirectional"))
    )
    (net (code "132") (name "unconnected-(U1F-PS_DDR_DQS_P2_502-PadR2)") (class "Default")
      (node (ref "U1") (pin "R2") (pinfunction "PS_DDR_DQS_P2_502_R2") (pintype "bidirectional"))
    )
    (net (code "133") (name "unconnected-(U1F-PS_DDR_DQS_P3_502-PadW5)") (class "Default")
      (node (ref "U1") (pin "W5") (pinfunction "PS_DDR_DQS_P3_502_W5") (pintype "bidirectional"))
    )
    (net (code "134") (name "unconnected-(U1F-PS_DDR_DRST_B_502-PadB4)") (class "Default")
      (node (ref "U1") (pin "B4") (pinfunction "PS_DDR_DRST_B_502_B4") (pintype "output"))
    )
    (net (code "135") (name "unconnected-(U1F-PS_DDR_ODT_502-PadN5)") (class "Default")
      (node (ref "U1") (pin "N5") (pinfunction "PS_DDR_ODT_502_N5") (pintype "output"))
    )
    (net (code "136") (name "unconnected-(U1F-PS_DDR_VREF0_502-PadH6)") (class "Default")
      (node (ref "U1") (pin "H6") (pinfunction "PS_DDR_VREF0_502_H6") (pintype "input"))
    )
    (net (code "137") (name "unconnected-(U1F-PS_DDR_VREF1_502-PadP6)") (class "Default")
      (node (ref "U1") (pin "P6") (pinfunction "PS_DDR_VREF1_502_P6") (pintype "input"))
    )
    (net (code "138") (name "unconnected-(U1F-PS_DDR_VRN_502-PadG5)") (class "Default")
      (node (ref "U1") (pin "G5") (pinfunction "PS_DDR_VRN_502_G5") (pintype "output"))
    )
    (net (code "139") (name "unconnected-(U1F-PS_DDR_VRP_502-PadH5)") (class "Default")
      (node (ref "U1") (pin "H5") (pinfunction "PS_DDR_VRP_502_H5") (pintype "output"))
    )
    (net (code "140") (name "unconnected-(U2-NC(A15)-PadM7)") (class "Default")
      (node (ref "U2") (pin "M7") (pinfunction "NC(A15)_M7") (pintype "passive"))
    )
    (net (code "141") (name "unconnected-(U2-NC1-PadJ1)") (class "Default")
      (node (ref "U2") (pin "J1") (pinfunction "NC1_J1") (pintype "passive"))
    )
    (net (code "142") (name "unconnected-(U2-NC2-PadJ9)") (class "Default")
      (node (ref "U2") (pin "J9") (pinfunction "NC2_J9") (pintype "passive"))
    )
    (net (code "143") (name "unconnected-(U2-NC3-PadL1)") (class "Default")
      (node (ref "U2") (pin "L1") (pinfunction "NC3_L1") (pintype "passive"))
    )
    (net (code "144") (name "unconnected-(U2-NC4-PadL9)") (class "Default")
      (node (ref "U2") (pin "L9") (pinfunction "NC4_L9") (pintype "passive"))
    )
    (net (code "145") (name "unconnected-(U2-ZQ-PadL8)") (class "Default")
      (node (ref "U2") (pin "L8") (pinfunction "ZQ_L8") (pintype "passive"))
    )
  )
)
